# WirelessModule.net
KiCad netlist of a schematic drawn in Altium Designer
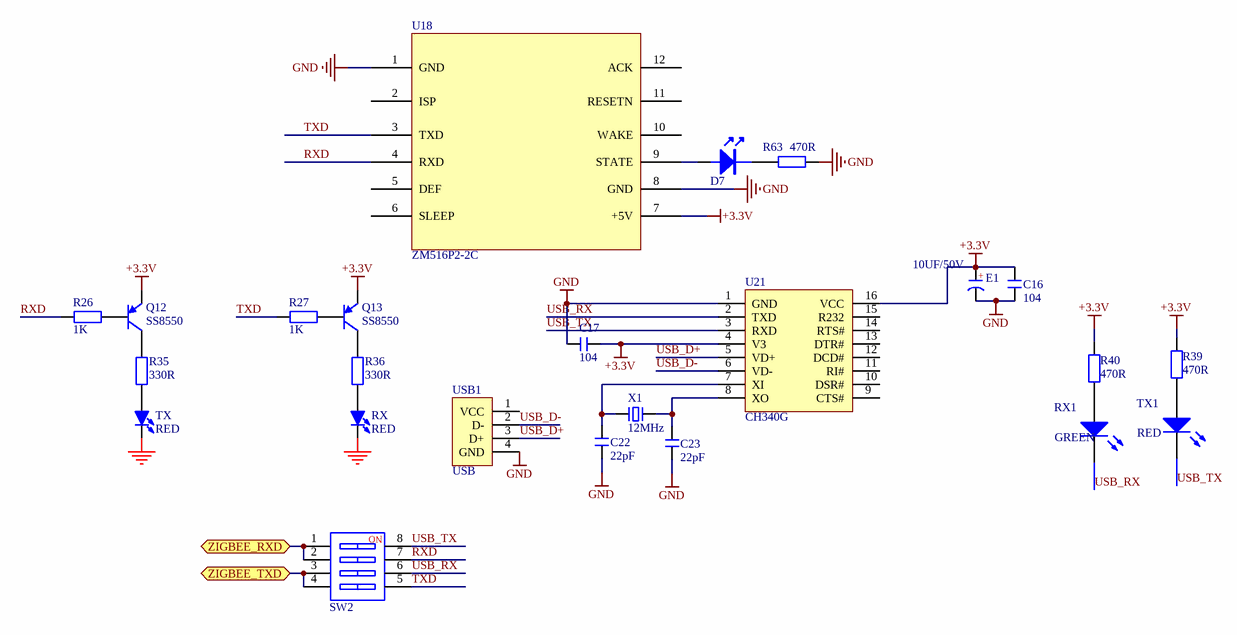
[diagram p0: WirelessModule.SchDoc]

(export (version "E")
  (design (tool "Eeschema 10.0.6"))
  (components
    (comp (ref "C16")
      (value "104")
      (footprint "C 0805")
      (description "无极性贴片电容")
      (fields (field (name "版权归属") "源创客"))
      (libsource (lib "电阻-电容-电感") (part "C"))
    )
    (comp (ref "C17")
      (value "104")
      (footprint "C 0805")
      (description "无极性贴片电容")
      (fields (field (name "版权归属") "源创客"))
      (libsource (lib "电阻-电容-电感") (part "C"))
    )
    (comp (ref "C22")
      (value "22pF")
      (footprint "C 0805")
      (description "无极性贴片电容")
      (fields (field (name "版权归属") "源创客"))
      (libsource (lib "电阻-电容-电感") (part "C"))
    )
    (comp (ref "C23")
      (value "22pF")
      (footprint "C 0805")
      (description "无极性贴片电容")
      (fields (field (name "版权归属") "源创客"))
      (libsource (lib "电阻-电容-电感") (part "C"))
    )
    (comp (ref "D7") (value "RED") (footprint "LED 3MM-B") (libsource (lib "CCDXPLIB") (part "LED")))
    (comp (ref "E1")
      (value "10UF/50V")
      (footprint "CAP 2.0*5*11")
      (description "直插电解电容")
      (fields (field (name "版权归属") "源创客"))
      (libsource (lib "电阻-电容-电感") (part "C-CAP"))
    )
    (comp (ref "Q12")
      (value "SS8550")
      (footprint "SOT23-3N")
      (description "高频放大-PNP型")
      (fields (field (name "版权归属") "源创客"))
      (libsource (lib "三极管") (part "8550-SMD"))
    )
    (comp (ref "Q13")
      (value "SS8550")
      (footprint "SOT23-3N")
      (description "高频放大-PNP型")
      (fields (field (name "版权归属") "源创客"))
      (libsource (lib "三极管") (part "8550-SMD"))
    )
    (comp (ref "R26")
      (value "1K")
      (footprint "R 0805-HP")
      (description "贴片电阻")
      (fields (field (name "版权归属") "源创客"))
      (libsource (lib "电阻-电容-电感") (part "R"))
    )
    (comp (ref "R27")
      (value "1K")
      (footprint "R 0805-HP")
      (description "贴片电阻")
      (fields (field (name "版权归属") "源创客"))
      (libsource (lib "电阻-电容-电感") (part "R"))
    )
    (comp (ref "R35")
      (value "330R")
      (footprint "R 0805-HP")
      (description "贴片电阻")
      (fields (field (name "版权归属") "源创客"))
      (libsource (lib "电阻-电容-电感") (part "R"))
    )
    (comp (ref "R36")
      (value "330R")
      (footprint "R 0805-HP")
      (description "贴片电阻")
      (fields (field (name "版权归属") "源创客"))
      (libsource (lib "电阻-电容-电感") (part "R"))
    )
    (comp (ref "R39") (value "470R") (footprint "R 0805") (libsource (lib "any") (part "Res1")))
    (comp (ref "R40") (value "470R") (footprint "R 0805") (libsource (lib "any") (part "Res1")))
    (comp (ref "R63")
      (value "470R")
      (footprint "R 0805")
      (description "贴片电阻")
      (fields (field (name "版权归属") "源创客"))
      (libsource (lib "电阻-电容-电感") (part "R"))
    )
    (comp (ref "RX")
      (value "RED")
      (footprint "LED 3MM-R")
      (description "5mm插件LED")
      (fields (field (name "版权归属") "源创客"))
      (libsource (lib "LED") (part "LED-5MM"))
    )
    (comp (ref "RX1") (value "GREEN") (footprint "LED 0805R") (libsource (lib "any") (part "LED")))
    (comp (ref "SW2")
      (value "CSW-4P")
      (footprint "CSW1.27 SMD-4P")
      (description "4路编码开关")
      (fields (field (name "版权归属") "源创客"))
      (libsource (lib "按键-开关") (part "CSW-4P"))
    )
    (comp (ref "TX")
      (value "RED")
      (footprint "LED 3MM-R")
      (description "5mm插件LED")
      (fields (field (name "版权归属") "源创客"))
      (libsource (lib "LED") (part "LED-5MM"))
    )
    (comp (ref "TX1") (value "RED") (footprint "LED 0805R") (libsource (lib "any") (part "LED")))
    (comp (ref "U18")
      (value "ZM516P2-2C")
      (footprint "ZM5168XP1-1C_ZJ")
      (libsource (lib "模块") (part "ZM516P2-2C转接"))
    )
    (comp (ref "U21") (value "CH340G") (footprint "SO16") (libsource (lib "YS-F1Pro开发板主板") (part "CH340G")))
    (comp (ref "USB1")
      (value "USB")
      (footprint "USB-B/S_A")
      (description "USB-A型母接口")
      (fields (field (name "版权归属") "源创客"))
      (libsource (lib "接口类") (part "USB-A/S"))
    )
    (comp (ref "X1")
      (value "12MHz")
      (footprint "XTAL-5032 - 2P")
      (description "2脚晶振")
      (fields (field (name "版权归属") "源创客"))
      (libsource (lib "保险丝-晶振") (part "XTAL-2"))
    )
  )
  (nets
    (net (code "1") (name "+3.3V") (class "Default")
      (node (ref "C16") (pin "2") (pinfunction "2_2") (pintype "passive"))
      (node (ref "C17") (pin "1") (pinfunction "1_1") (pintype "passive"))
      (node (ref "E1") (pin "1") (pinfunction "A_1") (pintype "passive"))
      (node (ref "Q12") (pin "2") (pinfunction "E_2") (pintype "passive"))
      (node (ref "Q13") (pin "2") (pinfunction "E_2") (pintype "passive"))
      (node (ref "R39") (pin "2") (pinfunction "2_2") (pintype "passive"))
      (node (ref "R40") (pin "2") (pinfunction "2_2") (pintype "passive"))
      (node (ref "U18") (pin "7") (pinfunction "+5V_7") (pintype "passive"))
      (node (ref "U21") (pin "16") (pinfunction "VCC_16") (pintype "passive"))
      (node (ref "U21") (pin "4") (pinfunction "V3_4") (pintype "passive"))
    )
    (net (code "2") (name "/RXD") (class "Default")
      (node (ref "R26") (pin "1") (pinfunction "1_1") (pintype "passive"))
      (node (ref "SW2") (pin "7") (pinfunction "7_7") (pintype "passive"))
      (node (ref "U18") (pin "4") (pinfunction "RXD_4") (pintype "passive"))
    )
    (net (code "3") (name "/TXD") (class "Default")
      (node (ref "R27") (pin "1") (pinfunction "1_1") (pintype "passive"))
      (node (ref "SW2") (pin "5") (pinfunction "5_5") (pintype "passive"))
      (node (ref "U18") (pin "3") (pinfunction "TXD_3") (pintype "passive"))
    )
    (net (code "4") (name "/USB_D+") (class "Default")
      (node (ref "U21") (pin "5") (pinfunction "VD+_5") (pintype "passive"))
      (node (ref "USB1") (pin "3") (pinfunction "D+_3") (pintype "passive"))
    )
    (net (code "5") (name "/USB_D-") (class "Default")
      (node (ref "U21") (pin "6") (pinfunction "VD-_6") (pintype "passive"))
      (node (ref "USB1") (pin "2") (pinfunction "D-_2") (pintype "passive"))
    )
    (net (code "6") (name "/USB_RX") (class "Default")
      (node (ref "RX1") (pin "2") (pinfunction "K_2") (pintype "passive"))
      (node (ref "SW2") (pin "6") (pinfunction "6_6") (pintype "passive"))
      (node (ref "U21") (pin "2") (pinfunction "TXD_2") (pintype "passive"))
    )
    (net (code "7") (name "/USB_TX") (class "Default")
      (node (ref "SW2") (pin "8") (pinfunction "8_8") (pintype "passive"))
      (node (ref "TX1") (pin "2") (pinfunction "K_2") (pintype "passive"))
      (node (ref "U21") (pin "3") (pinfunction "RXD_3") (pintype "passive"))
    )
    (net (code "8") (name "/ZIGBEE_RXD") (class "Default")
      (node (ref "SW2") (pin "1") (pinfunction "1_1") (pintype "passive"))
      (node (ref "SW2") (pin "2") (pinfunction "2_2") (pintype "passive"))
    )
    (net (code "9") (name "/ZIGBEE_TXD") (class "Default")
      (node (ref "SW2") (pin "3") (pinfunction "3_3") (pintype "passive"))
      (node (ref "SW2") (pin "4") (pinfunction "4_4") (pintype "passive"))
    )
    (net (code "10") (name "GND") (class "Default")
      (node (ref "C16") (pin "1") (pinfunction "1_1") (pintype "passive"))
      (node (ref "C17") (pin "2") (pinfunction "2_2") (pintype "passive"))
      (node (ref "C22") (pin "1") (pinfunction "1_1") (pintype "passive"))
      (node (ref "C23") (pin "1") (pinfunction "1_1") (pintype "passive"))
      (node (ref "E1") (pin "2") (pinfunction "K_2") (pintype "passive"))
      (node (ref "R63") (pin "2") (pinfunction "2_2") (pintype "passive"))
      (node (ref "RX") (pin "2") (pinfunction "K_2") (pintype "passive"))
      (node (ref "TX") (pin "2") (pinfunction "K_2") (pintype "passive"))
      (node (ref "U18") (pin "1") (pinfunction "GND_1") (pintype "passive"))
      (node (ref "U18") (pin "8") (pinfunction "GND_8") (pintype "passive"))
      (node (ref "U21") (pin "1") (pinfunction "GND_1") (pintype "passive"))
      (node (ref "USB1") (pin "4") (pinfunction "GND_4") (pintype "passive"))
    )
    (net (code "11") (name "Net-(D7-Pad2)") (class "Default")
      (node (ref "D7") (pin "2") (pinfunction "2_2") (pintype "passive"))
      (node (ref "R63") (pin "1") (pinfunction "1_1") (pintype "passive"))
    )
    (net (code "12") (name "Net-(Q12-B)") (class "Default")
      (node (ref "Q12") (pin "1") (pinfunction "B_1") (pintype "passive"))
      (node (ref "R26") (pin "2") (pinfunction "2_2") (pintype "passive"))
    )
    (net (code "13") (name "Net-(Q12-C)") (class "Default")
      (node (ref "Q12") (pin "3") (pinfunction "C_3") (pintype "passive"))
      (node (ref "R35") (pin "1") (pinfunction "1_1") (pintype "passive"))
    )
    (net (code "14") (name "Net-(Q13-B)") (class "Default")
      (node (ref "Q13") (pin "1") (pinfunction "B_1") (pintype "passive"))
      (node (ref "R27") (pin "2") (pinfunction "2_2") (pintype "passive"))
    )
    (net (code "15") (name "Net-(Q13-C)") (class "Default")
      (node (ref "Q13") (pin "3") (pinfunction "C_3") (pintype "passive"))
      (node (ref "R36") (pin "1") (pinfunction "1_1") (pintype "passive"))
    )
    (net (code "16") (name "Net-(RX-A)") (class "Default")
      (node (ref "R36") (pin "2") (pinfunction "2_2") (pintype "passive"))
      (node (ref "RX") (pin "1") (pinfunction "A_1") (pintype "passive"))
    )
    (net (code "17") (name "Net-(RX1-A)") (class "Default")
      (node (ref "R40") (pin "1") (pinfunction "1_1") (pintype "passive"))
      (node (ref "RX1") (pin "1") (pinfunction "A_1") (pintype "passive"))
    )
    (net (code "18") (name "Net-(TX-A)") (class "Default")
      (node (ref "R35") (pin "2") (pinfunction "2_2") (pintype "passive"))
      (node (ref "TX") (pin "1") (pinfunction "A_1") (pintype "passive"))
    )
    (net (code "19") (name "Net-(TX1-A)") (class "Default")
      (node (ref "R39") (pin "1") (pinfunction "1_1") (pintype "passive"))
      (node (ref "TX1") (pin "1") (pinfunction "A_1") (pintype "passive"))
    )
    (net (code "20") (name "Net-(U18-STATE)") (class "Default")
      (node (ref "D7") (pin "1") (pinfunction "1_1") (pintype "passive"))
      (node (ref "U18") (pin "9") (pinfunction "STATE_9") (pintype "passive"))
    )
    (net (code "21") (name "Net-(U21-XI)") (class "Default")
      (node (ref "C22") (pin "2") (pinfunction "2_2") (pintype "passive"))
      (node (ref "U21") (pin "7") (pinfunction "XI_7") (pintype "passive"))
      (node (ref "X1") (pin "1") (pinfunction "1_1") (pintype "passive"))
    )
    (net (code "22") (name "Net-(U21-XO)") (class "Default")
      (node (ref "C23") (pin "2") (pinfunction "2_2") (pintype "passive"))
      (node (ref "U21") (pin "8") (pinfunction "XO_8") (pintype "passive"))
      (node (ref "X1") (pin "2") (pinfunction "2_2") (pintype "passive"))
    )
    (net (code "23") (name "unconnected-(U18-ACK-Pad12)") (class "Default")
      (node (ref "U18") (pin "12") (pinfunction "ACK_12") (pintype "passive"))
    )
    (net (code "24") (name "unconnected-(U18-DEF-Pad5)") (class "Default")
      (node (ref "U18") (pin "5") (pinfunction "DEF_5") (pintype "passive"))
    )
    (net (code "25") (name "unconnected-(U18-ISP-Pad2)") (class "Default")
      (node (ref "U18") (pin "2") (pinfunction "ISP_2") (pintype "passive"))
    )
    (net (code "26") (name "unconnected-(U18-RESETN-Pad11)") (class "Default")
      (node (ref "U18") (pin "11") (pinfunction "RESETN_11") (pintype "passive"))
    )
    (net (code "27") (name "unconnected-(U18-SLEEP-Pad6)") (class "Default")
      (node (ref "U18") (pin "6") (pinfunction "SLEEP_6") (pintype "passive"))
    )
    (net (code "28") (name "unconnected-(U18-WAKE-Pad10)") (class "Default")
      (node (ref "U18") (pin "10") (pinfunction "WAKE_10") (pintype "passive"))
    )
    (net (code "29") (name "unconnected-(U21-CTS#-Pad9)") (class "Default")
      (node (ref "U21") (pin "9") (pinfunction "CTS#_9") (pintype "passive"))
    )
    (net (code "30") (name "unconnected-(U21-DCD#-Pad12)") (class "Default")
      (node (ref "U21") (pin "12") (pinfunction "DCD#_12") (pintype "passive"))
    )
    (net (code "31") (name "unconnected-(U21-DSR#-Pad10)") (class "Default")
      (node (ref "U21") (pin "10") (pinfunction "DSR#_10") (pintype "passive"))
    )
    (net (code "32") (name "unconnected-(U21-DTR#-Pad13)") (class "Default")
      (node (ref "U21") (pin "13") (pinfunction "DTR#_13") (pintype "passive"))
    )
    (net (code "33") (name "unconnected-(U21-R232-Pad15)") (class "Default")
      (node (ref "U21") (pin "15") (pinfunction "R232_15") (pintype "passive"))
    )
    (net (code "34") (name "unconnected-(U21-RI#-Pad11)") (class "Default")
      (node (ref "U21") (pin "11") (pinfunction "RI#_11") (pintype "passive"))
    )
    (net (code "35") (name "unconnected-(U21-RTS#-Pad14)") (class "Default")
      (node (ref "U21") (pin "14") (pinfunction "RTS#_14") (pintype "passive"))
    )
    (net (code "36") (name "unconnected-(USB1-VCC-Pad1)") (class "Default")
      (node (ref "USB1") (pin "1") (pinfunction "VCC_1") (pintype "passive"))
    )
  )
)
